# 0827.net
KiCad netlist of a schematic drawn in Altium Designer
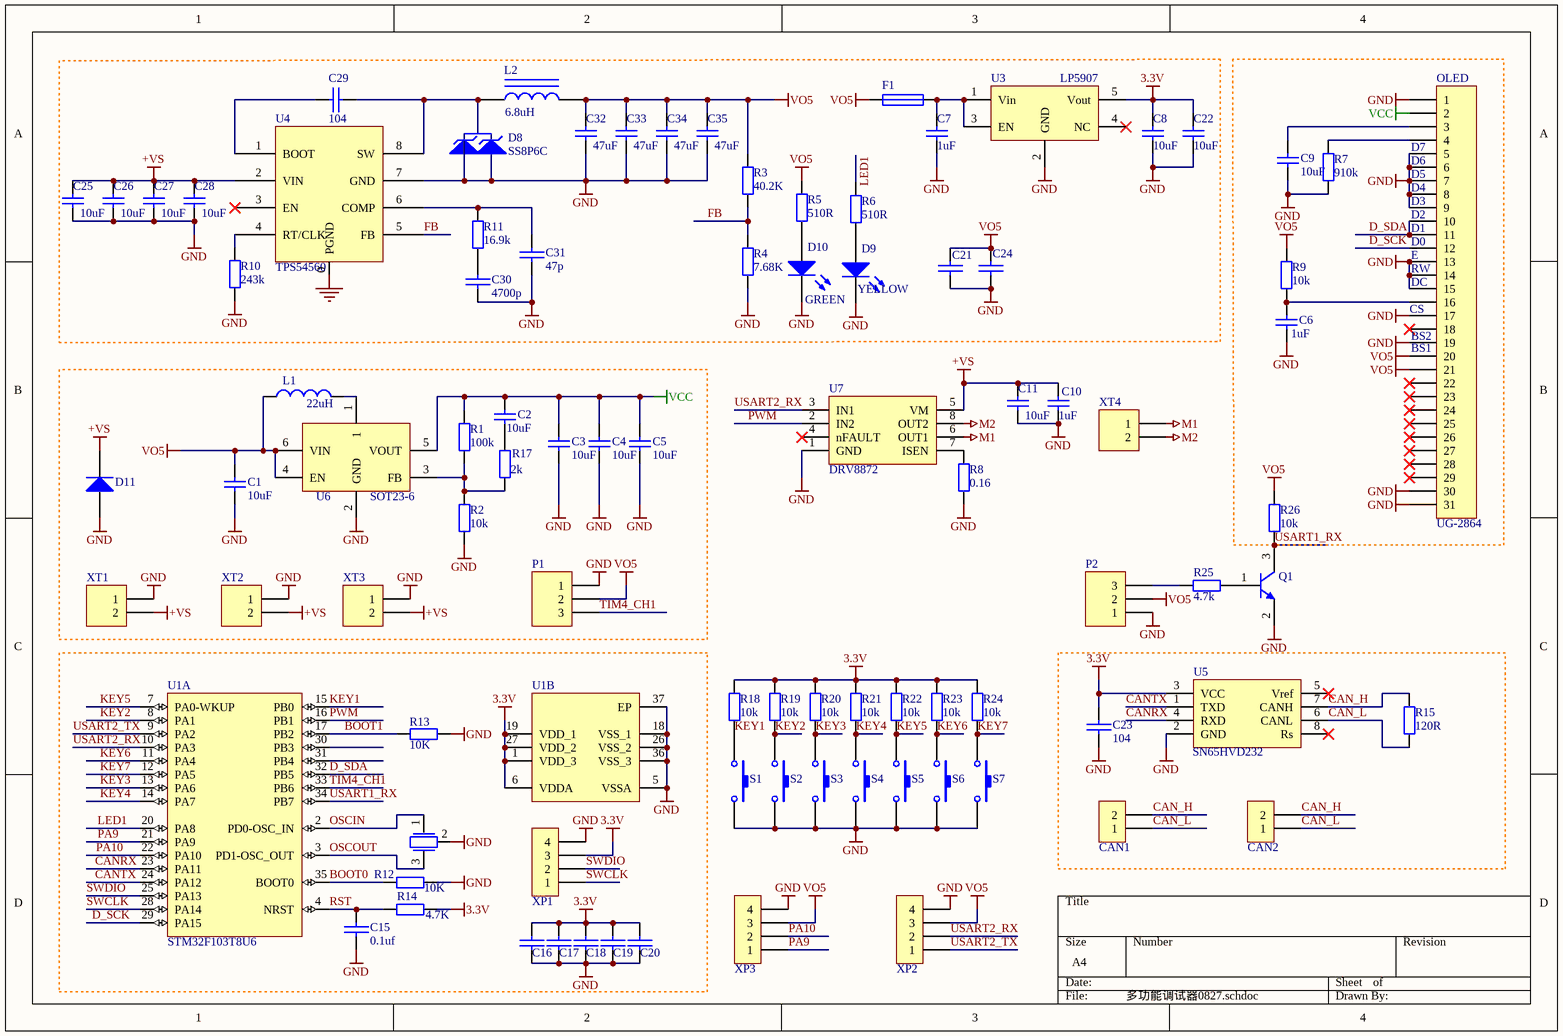
[diagram p0: 多功能调试器0827.schdoc]

(export (version "E")
  (design (tool "Eeschema 10.0.6"))
  (components
    (comp (ref "1")
      (value "~")
      (footprint "XTAL_SMD_3215_2")
      (description "贴片晶振")
      (libsource (lib "Fszhang") (part "XTAL-3PIN"))
    )
    (comp (ref "C1")
      (value "10uF")
      (footprint "1210C")
      (description "Capacitor")
      (fields (field (name "Comment") "2.2uF") (field (name "PUBLISHER") "Altium Limited"))
      (libsource (lib "Miscellaneous Devices") (part "Cap"))
    )
    (comp (ref "C2")
      (value "10uF")
      (footprint "0805C")
      (description "Capacitor")
      (fields (field (name "Comment") "22uF") (field (name "PUBLISHER") "Altium Limited"))
      (libsource (lib "Miscellaneous Devices") (part "Cap"))
    )
    (comp (ref "C3")
      (value "10uF")
      (footprint "0805C")
      (description "Capacitor")
      (fields (field (name "Comment") "22uF") (field (name "PUBLISHER") "Altium Limited"))
      (libsource (lib "Miscellaneous Devices") (part "Cap"))
    )
    (comp (ref "C4")
      (value "10uF")
      (footprint "1210C")
      (description "Capacitor")
      (fields (field (name "Comment") "22uF") (field (name "PUBLISHER") "Altium Limited"))
      (libsource (lib "Miscellaneous Devices") (part "Cap"))
    )
    (comp (ref "C5")
      (value "10uF")
      (footprint "1210C")
      (description "Capacitor")
      (fields (field (name "Comment") "22uF") (field (name "PUBLISHER") "Altium Limited"))
      (libsource (lib "Miscellaneous Devices") (part "Cap"))
    )
    (comp (ref "C6")
      (value "1uF")
      (footprint "0805C")
      (description "Capacitor")
      (fields (field (name "PUBLISHER") "Altium Limited"))
      (libsource (lib "Miscellaneous Devices") (part "Cap"))
    )
    (comp (ref "C7")
      (value "1uF")
      (footprint "0805C")
      (description "Capacitor")
      (fields (field (name "PUBLISHER") "Altium Limited"))
      (libsource (lib "Miscellaneous Devices") (part "Cap"))
    )
    (comp (ref "C8")
      (value "10uF")
      (footprint "0805C")
      (description "Capacitor")
      (fields (field (name "Comment") "1uF") (field (name "PUBLISHER") "Altium Limited"))
      (libsource (lib "Miscellaneous Devices") (part "Cap"))
    )
    (comp (ref "C9")
      (value "10uF")
      (footprint "1210C")
      (description "Capacitor")
      (fields (field (name "Comment") "22uF") (field (name "PUBLISHER") "Altium Limited"))
      (libsource (lib "Miscellaneous Devices") (part "Cap"))
    )
    (comp (ref "C10")
      (value "1uF")
      (footprint "0805C")
      (description "Capacitor")
      (fields (field (name "PUBLISHER") "Altium Limited"))
      (libsource (lib "Miscellaneous Devices") (part "Cap"))
    )
    (comp (ref "C11")
      (value "10uF")
      (footprint "1210C")
      (description "Capacitor")
      (fields (field (name "Comment") "22uF") (field (name "PUBLISHER") "Altium Limited"))
      (libsource (lib "Miscellaneous Devices") (part "Cap"))
    )
    (comp (ref "C15")
      (value "CAP")
      (footprint "0603C")
      (fields (field (name "ALTIUM_UNNAMED_1") "0.1uf"))
      (libsource (lib "My_SCH_Lib") (part "CAP"))
    )
    (comp (ref "C16") (value "~") (footprint "0603C") (libsource (lib "My_SCH_Lib") (part "CAP")))
    (comp (ref "C17") (value "104") (footprint "0603C") (libsource (lib "My_SCH_Lib") (part "CAP")))
    (comp (ref "C18") (value "104") (footprint "0603C") (libsource (lib "My_SCH_Lib") (part "CAP")))
    (comp (ref "C19") (value "104") (footprint "0603C") (libsource (lib "My_SCH_Lib") (part "CAP")))
    (comp (ref "C20") (value "104") (footprint "0603C") (libsource (lib "My_SCH_Lib") (part "CAP")))
    (comp (ref "C21") (value "104") (footprint "0603C") (libsource (lib "My_SCH_Lib") (part "CAP")))
    (comp (ref "C22")
      (value "10uF")
      (footprint "0805C")
      (description "Capacitor")
      (fields (field (name "Comment") "1uF") (field (name "PUBLISHER") "Altium Limited"))
      (libsource (lib "Miscellaneous Devices") (part "Cap"))
    )
    (comp (ref "C23")
      (value "CAP")
      (footprint "0402C")
      (fields (field (name "ALTIUM_UNNAMED_1") "104"))
      (libsource (lib "My_SCH_Lib") (part "CAP"))
    )
    (comp (ref "C24") (value "104") (footprint "0805C") (libsource (lib "My_SCH_Lib") (part "CAP")))
    (comp (ref "C25")
      (value "10uF")
      (footprint "1210C")
      (description "Capacitor")
      (fields (field (name "Comment") "22uF") (field (name "PUBLISHER") "Altium Limited"))
      (libsource (lib "Miscellaneous Devices") (part "Cap"))
    )
    (comp (ref "C26")
      (value "10uF")
      (footprint "1210C")
      (description "Capacitor")
      (fields (field (name "Comment") "22uF") (field (name "PUBLISHER") "Altium Limited"))
      (libsource (lib "Miscellaneous Devices") (part "Cap"))
    )
    (comp (ref "C27")
      (value "10uF")
      (footprint "1210C")
      (description "Capacitor")
      (fields (field (name "Comment") "22uF") (field (name "PUBLISHER") "Altium Limited"))
      (libsource (lib "Miscellaneous Devices") (part "Cap"))
    )
    (comp (ref "C28")
      (value "10uF")
      (footprint "1210C")
      (description "Capacitor")
      (fields (field (name "Comment") "22uF") (field (name "PUBLISHER") "Altium Limited"))
      (libsource (lib "Miscellaneous Devices") (part "Cap"))
    )
    (comp (ref "C29")
      (value "104")
      (footprint "0603C")
      (description "Capacitor")
      (libsource (lib "*") (part "CAP"))
    )
    (comp (ref "C30")
      (value "4700p")
      (footprint "0603C")
      (description "Capacitor")
      (libsource (lib "*") (part "CAP"))
    )
    (comp (ref "C31")
      (value "47p")
      (footprint "0603C")
      (description "Capacitor")
      (libsource (lib "*") (part "CAP"))
    )
    (comp (ref "C32")
      (value "47uF")
      (footprint "1210C")
      (description "Capacitor")
      (fields (field (name "Comment") "22uF") (field (name "PUBLISHER") "Altium Limited"))
      (libsource (lib "Miscellaneous Devices") (part "Cap"))
    )
    (comp (ref "C33")
      (value "47uF")
      (footprint "1210C")
      (description "Capacitor")
      (fields (field (name "Comment") "22uF") (field (name "PUBLISHER") "Altium Limited"))
      (libsource (lib "Miscellaneous Devices") (part "Cap"))
    )
    (comp (ref "C34")
      (value "47uF")
      (footprint "1210C")
      (description "Capacitor")
      (fields (field (name "Comment") "22uF") (field (name "PUBLISHER") "Altium Limited"))
      (libsource (lib "Miscellaneous Devices") (part "Cap"))
    )
    (comp (ref "C35")
      (value "47uF")
      (footprint "1210C")
      (description "Capacitor")
      (fields (field (name "Comment") "22uF") (field (name "PUBLISHER") "Altium Limited"))
      (libsource (lib "Miscellaneous Devices") (part "Cap"))
    )
    (comp (ref "CAN1")
      (value "CAN")
      (footprint "GH1.25-WS-2P")
      (description "jointbar")
      (libsource (lib "Integrated_Library1") (part "SIP2"))
    )
    (comp (ref "CAN2")
      (value "CAN")
      (footprint "GH1.25-WS-2P")
      (description "jointbar")
      (libsource (lib "Integrated_Library1") (part "SIP2"))
    )
    (comp (ref "D8") (value "SS8P6C") (footprint "TO-227") (libsource (lib "步兵2020") (part "SS8P6C")))
    (comp (ref "D9")
      (value "LED0")
      (footprint "LED_0805_B")
      (description "Typical INFRARED GaAs LED")
      (fields (field (name "PUBLISHER") "Altium Limited"))
      (libsource (lib "Miscellaneous Devices") (part "LED0"))
    )
    (comp (ref "D10")
      (value "LED0")
      (footprint "LED_0805_B")
      (description "Typical INFRARED GaAs LED")
      (fields (field (name "PUBLISHER") "Altium Limited"))
      (libsource (lib "Miscellaneous Devices") (part "LED0"))
    )
    (comp (ref "D11")
      (value "~")
      (footprint "DO214_SMA")
      (description "1 Amp General Purpose Rectifier")
      (fields (field (name "PUBLISHER") "Altium Limited"))
      (libsource (lib "Miscellaneous Devices") (part "Diode 1N4001"))
    )
    (comp (ref "F1")
      (value "~")
      (footprint "0805R")
      (description "Fuse")
      (fields (field (name "PUBLISHER") "Altium Limited"))
      (libsource (lib "Miscellaneous Devices") (part "Fuse 1"))
    )
    (comp (ref "L1")
      (value "22uH")
      (footprint "L6×6")
      (description "Inductor")
      (fields (field (name "Comment") "10uH") (field (name "PUBLISHER") "Altium Limited"))
      (libsource (lib "Miscellaneous Devices") (part "Inductor"))
    )
    (comp (ref "L2")
      (value "6.8uH")
      (footprint "L7-7")
      (description "Magnetic-Core Inductor")
      (fields (field (name "PUBLISHER") "Altium Limited"))
      (libsource (lib "Miscellaneous Devices") (part "Inductor Iron"))
    )
    (comp (ref "OLED")
      (value "UG-2864")
      (footprint "OLED")
      (description "Header, 30-Pin")
      (fields (field (name "PUBLISHER") "Altium Limited"))
      (libsource (lib "VFD25650") (part "Header 30"))
    )
    (comp (ref "P1")
      (value "~")
      (footprint "HDR2.54-LI-3P")
      (description "Header, 3-Pin")
      (fields (field (name "PUBLISHER") "Altium Limited"))
      (libsource (lib "") (part "Header 3_1"))
    )
    (comp (ref "P2")
      (value "~")
      (footprint "HDR2.54-LI-3P")
      (description "Header, 3-Pin")
      (fields (field (name "PUBLISHER") "Altium Limited"))
      (libsource (lib "Miscellaneous Connectors") (part "Header 3"))
    )
    (comp (ref "Q1")
      (value "~")
      (footprint "SOT23_3")
      (description "NPN Bipolar Transistor")
      (fields (field (name "PUBLISHER") "Altium Limited"))
      (libsource (lib "Miscellaneous Devices") (part "NPN"))
    )
    (comp (ref "R1")
      (value "100k")
      (footprint "0805R")
      (description "Resistor")
      (fields (field (name "PUBLISHER") "Altium Limited"))
      (libsource (lib "") (part "Res2_2"))
    )
    (comp (ref "R2")
      (value "10k")
      (footprint "0805R")
      (description "Resistor")
      (fields (field (name "PUBLISHER") "Altium Limited"))
      (libsource (lib "") (part "Res2_2"))
    )
    (comp (ref "R3")
      (value "40.2K")
      (footprint "0603R")
      (description "贴片电阻")
      (fields (field (name "Comment") "Res1") (field (name "PUBLISHER") "Altium Limited"))
      (libsource (lib "Fszhang") (part "Res1"))
    )
    (comp (ref "R4")
      (value "7.68K")
      (footprint "0603R")
      (description "贴片电阻")
      (fields (field (name "Comment") "Res1") (field (name "PUBLISHER") "Altium Limited"))
      (libsource (lib "Fszhang") (part "Res1"))
    )
    (comp (ref "R5")
      (value "510R")
      (footprint "0805R")
      (description "贴片电阻")
      (fields (field (name "Comment") "Res1") (field (name "PUBLISHER") "Altium Limited"))
      (libsource (lib "Fszhang") (part "Res1"))
    )
    (comp (ref "R6")
      (value "510R")
      (footprint "0805R")
      (description "贴片电阻")
      (fields (field (name "Comment") "Res1") (field (name "PUBLISHER") "Altium Limited"))
      (libsource (lib "Fszhang") (part "Res1"))
    )
    (comp (ref "R7")
      (value "910k")
      (footprint "0805R")
      (description "Resistor")
      (fields (field (name "PUBLISHER") "Altium Limited"))
      (libsource (lib "") (part "Res2_2"))
    )
    (comp (ref "R8")
      (value "0.16")
      (footprint "1210R")
      (description "Resistor")
      (fields (field (name "PUBLISHER") "Altium Limited"))
      (libsource (lib "") (part "Res2_2"))
    )
    (comp (ref "R9")
      (value "10k")
      (footprint "0805R")
      (description "Resistor")
      (fields (field (name "PUBLISHER") "Altium Limited"))
      (libsource (lib "2017.2步兵主控") (part "Res2"))
    )
    (comp (ref "R10")
      (value "243k")
      (footprint "0603R")
      (description "Resistor")
      (fields (field (name "PUBLISHER") "Altium Limited"))
      (libsource (lib "2017.2步兵主控") (part "Res2"))
    )
    (comp (ref "R11")
      (value "16.9k")
      (footprint "0603R")
      (description "Resistor")
      (fields (field (name "PUBLISHER") "Altium Limited"))
      (libsource (lib "2017.2步兵主控") (part "Res2"))
    )
    (comp (ref "R12")
      (value "10K")
      (footprint "0603R")
      (description "贴片电阻")
      (fields (field (name "Comment") "Res1") (field (name "PUBLISHER") "Altium Limited"))
      (libsource (lib "") (part "Res1_1"))
    )
    (comp (ref "R13")
      (value "10K")
      (footprint "0603R")
      (description "贴片电阻")
      (fields (field (name "Comment") "Res1") (field (name "PUBLISHER") "Altium Limited"))
      (libsource (lib "") (part "Res1_1"))
    )
    (comp (ref "R14")
      (value "4.7K")
      (footprint "0603R")
      (description "贴片电阻")
      (fields (field (name "Comment") "Res1") (field (name "PUBLISHER") "Altium Limited"))
      (libsource (lib "") (part "Res1_1"))
    )
    (comp (ref "R15")
      (value "120R")
      (footprint "0603C")
      (description "贴片电阻")
      (fields (field (name "Comment") "Res1") (field (name "PUBLISHER") "Altium Limited"))
      (libsource (lib "Fszhang") (part "Res1"))
    )
    (comp (ref "R17")
      (value "2k")
      (footprint "0805R")
      (description "Resistor")
      (fields (field (name "PUBLISHER") "Altium Limited"))
      (libsource (lib "") (part "Res2_2"))
    )
    (comp (ref "R18")
      (value "10k")
      (footprint "0805R")
      (description "Resistor")
      (fields (field (name "PUBLISHER") "Altium Limited"))
      (libsource (lib "2017.2步兵主控") (part "Res2"))
    )
    (comp (ref "R19")
      (value "10k")
      (footprint "0805R")
      (description "Resistor")
      (fields (field (name "PUBLISHER") "Altium Limited"))
      (libsource (lib "2017.2步兵主控") (part "Res2"))
    )
    (comp (ref "R20")
      (value "10k")
      (footprint "0805R")
      (description "Resistor")
      (fields (field (name "PUBLISHER") "Altium Limited"))
      (libsource (lib "2017.2步兵主控") (part "Res2"))
    )
    (comp (ref "R21")
      (value "10k")
      (footprint "0805R")
      (description "Resistor")
      (fields (field (name "PUBLISHER") "Altium Limited"))
      (libsource (lib "2017.2步兵主控") (part "Res2"))
    )
    (comp (ref "R22")
      (value "10k")
      (footprint "0805R")
      (description "Resistor")
      (fields (field (name "PUBLISHER") "Altium Limited"))
      (libsource (lib "2017.2步兵主控") (part "Res2"))
    )
    (comp (ref "R23")
      (value "10k")
      (footprint "0805R")
      (description "Resistor")
      (fields (field (name "PUBLISHER") "Altium Limited"))
      (libsource (lib "2017.2步兵主控") (part "Res2"))
    )
    (comp (ref "R24")
      (value "10k")
      (footprint "0805R")
      (description "Resistor")
      (fields (field (name "PUBLISHER") "Altium Limited"))
      (libsource (lib "2017.2步兵主控") (part "Res2"))
    )
    (comp (ref "R25")
      (value "4.7k")
      (footprint "0805R")
      (description "Resistor")
      (fields (field (name "PUBLISHER") "Altium Limited"))
      (libsource (lib "") (part "Res2_1"))
    )
    (comp (ref "R26")
      (value "10k")
      (footprint "0805R")
      (description "Resistor")
      (fields (field (name "PUBLISHER") "Altium Limited"))
      (libsource (lib "") (part "Res2_2"))
    )
    (comp (ref "S1")
      (value "SW-PB")
      (footprint "SW_PB_6*6")
      (description "Switch")
      (fields (field (name "PUBLISHER") "Altium Limited"))
      (libsource (lib "") (part "SW-PB_1"))
    )
    (comp (ref "S2")
      (value "SW-PB")
      (footprint "SW_PB_6*6")
      (description "Switch")
      (fields (field (name "PUBLISHER") "Altium Limited"))
      (libsource (lib "") (part "SW-PB_1"))
    )
    (comp (ref "S3")
      (value "SW-PB")
      (footprint "BUT12/B3F")
      (description "Switch")
      (fields (field (name "PUBLISHER") "Altium Limited"))
      (libsource (lib "Miscellaneous Devices") (part "SW-PB"))
    )
    (comp (ref "S4")
      (value "SW-PB")
      (footprint "BUT12/B3F")
      (description "Switch")
      (fields (field (name "PUBLISHER") "Altium Limited"))
      (libsource (lib "Miscellaneous Devices") (part "SW-PB"))
    )
    (comp (ref "S5")
      (value "SW-PB")
      (footprint "BUT12/B3F")
      (description "Switch")
      (fields (field (name "PUBLISHER") "Altium Limited"))
      (libsource (lib "Miscellaneous Devices") (part "SW-PB"))
    )
    (comp (ref "S6")
      (value "SW-PB")
      (footprint "BUT12/B3F")
      (description "Switch")
      (fields (field (name "PUBLISHER") "Altium Limited"))
      (libsource (lib "Miscellaneous Devices") (part "SW-PB"))
    )
    (comp (ref "S7")
      (value "SW-PB")
      (footprint "BUT12/B3F")
      (description "Switch")
      (fields (field (name "PUBLISHER") "Altium Limited"))
      (libsource (lib "Miscellaneous Devices") (part "SW-PB"))
    )
    (comp (ref "U1")
      (value "STM32F103T8U6")
      (footprint "VFQN36_N")
      (fields (field (name "PARTNUMBER") "STM32F103TBU6"))
      (libsource (lib "多功能调试器V1.0") (part "STM32F103TBU6"))
    )
    (comp (ref "U3") (value "LP5907") (footprint "SOT23_5") (libsource (lib "VFD25650") (part "LP5907")))
    (comp (ref "U4") (value "TPS54560") (footprint "SOIC8E") (libsource (lib "yuanlitu") (part "TPS54560")))
    (comp (ref "U5")
      (value "SN65HVD232")
      (footprint "SOp8")
      (libsource (lib "Robomasters") (part "SN65HVD232"))
    )
    (comp (ref "U6")
      (value "SOT23-6")
      (footprint "SOT23_6")
      (libsource (lib "yuanlitu") (part "未知电源芯片SOT23-6"))
    )
    (comp (ref "U7")
      (value "DRV8872")
      (footprint "SOIC8E")
      (libsource (lib "多功能调试器V1.0") (part "SN65HVD232_1"))
    )
    (comp (ref "XP1")
      (value "CON4")
      (footprint "GH1.25-WS-4P")
      (description "Connector")
      (libsource (lib "POWER_S_M") (part "CON4"))
    )
    (comp (ref "XP2")
      (value "CON4")
      (footprint "GH1.25-WS-4P")
      (description "Connector")
      (libsource (lib "POWER_S_M") (part "CON4"))
    )
    (comp (ref "XP3")
      (value "CON4")
      (footprint "GH1.25-WS-4P")
      (description "Connector")
      (libsource (lib "POWER_S_M") (part "CON4"))
    )
    (comp (ref "XT1")
      (value "~")
      (footprint "XT30PW-M")
      (description "Header, 2-Pin")
      (fields (field (name "PUBLISHER") "Altium Limited"))
      (libsource (lib "2017.2步兵主控") (part "Header 2"))
    )
    (comp (ref "XT2")
      (value "~")
      (footprint "XT30PW-M")
      (description "Header, 2-Pin")
      (fields (field (name "PUBLISHER") "Altium Limited"))
      (libsource (lib "2017.2步兵主控") (part "Header 2"))
    )
    (comp (ref "XT3")
      (value "~")
      (footprint "XT30PW-M")
      (description "Header, 2-Pin")
      (fields (field (name "PUBLISHER") "Altium Limited"))
      (libsource (lib "2017.2步兵主控") (part "Header 2"))
    )
    (comp (ref "XT4")
      (value "~")
      (footprint "XT30PW-M")
      (description "Header, 2-Pin")
      (fields (field (name "PUBLISHER") "Altium Limited"))
      (libsource (lib "2017.2步兵主控") (part "Header 2"))
    )
  )
  (nets
    (net (code "1") (name "+VS") (class "Default")
      (node (ref "C10") (pin "2") (pinfunction "2_2") (pintype "passive"))
      (node (ref "C11") (pin "1") (pinfunction "1_1") (pintype "passive"))
      (node (ref "C25") (pin "1") (pinfunction "1_1") (pintype "passive"))
      (node (ref "C26") (pin "1") (pinfunction "1_1") (pintype "passive"))
      (node (ref "C27") (pin "1") (pinfunction "1_1") (pintype "passive"))
      (node (ref "C28") (pin "1") (pinfunction "1_1") (pintype "passive"))
      (node (ref "D11") (pin "2") (pinfunction "K_2") (pintype "passive"))
      (node (ref "U4") (pin "2") (pinfunction "VIN_2") (pintype "passive"))
      (node (ref "U7") (pin "5") (pinfunction "VM_5") (pintype "passive"))
      (node (ref "XT1") (pin "2") (pinfunction "2_2") (pintype "passive"))
      (node (ref "XT2") (pin "2") (pinfunction "2_2") (pintype "passive"))
      (node (ref "XT3") (pin "2") (pinfunction "2_2") (pintype "passive"))
    )
    (net (code "2") (name "/BOOT0") (class "Default")
      (node (ref "R12") (pin "2") (pinfunction "2_2") (pintype "passive"))
      (node (ref "U1") (pin "35") (pinfunction "BOOT0_35") (pintype "bidirectional"))
    )
    (net (code "3") (name "/BOOT1") (class "Default")
      (node (ref "R13") (pin "2") (pinfunction "2_2") (pintype "passive"))
      (node (ref "U1") (pin "17") (pinfunction "PB2_17") (pintype "bidirectional"))
    )
    (net (code "4") (name "/CANRX") (class "Default")
      (node (ref "U1") (pin "23") (pinfunction "PA11_23") (pintype "bidirectional"))
      (node (ref "U5") (pin "4") (pinfunction "RXD_4") (pintype "passive"))
    )
    (net (code "5") (name "/CANTX") (class "Default")
      (node (ref "U1") (pin "24") (pinfunction "PA12_24") (pintype "bidirectional"))
      (node (ref "U5") (pin "1") (pinfunction "TXD_1") (pintype "passive"))
    )
    (net (code "6") (name "/CAN_H") (class "Default")
      (node (ref "CAN1") (pin "2") (pinfunction "2_2") (pintype "passive"))
      (node (ref "CAN2") (pin "2") (pinfunction "2_2") (pintype "passive"))
      (node (ref "R15") (pin "1") (pinfunction "1_1") (pintype "passive"))
      (node (ref "U5") (pin "7") (pinfunction "CANH_7") (pintype "passive"))
    )
    (net (code "7") (name "/CAN_L") (class "Default")
      (node (ref "CAN1") (pin "1") (pinfunction "1_1") (pintype "passive"))
      (node (ref "CAN2") (pin "1") (pinfunction "1_1") (pintype "passive"))
      (node (ref "R15") (pin "2") (pinfunction "2_2") (pintype "passive"))
      (node (ref "U5") (pin "6") (pinfunction "CANL_6") (pintype "passive"))
    )
    (net (code "8") (name "/D_SCK") (class "Default")
      (node (ref "OLED") (pin "12") (pinfunction "12_12") (pintype "passive"))
      (node (ref "U1") (pin "29") (pinfunction "PA15_29") (pintype "bidirectional"))
    )
    (net (code "9") (name "/D_SDA") (class "Default")
      (node (ref "OLED") (pin "10") (pinfunction "10_10") (pintype "passive"))
      (node (ref "OLED") (pin "11") (pinfunction "11_11") (pintype "passive"))
      (node (ref "U1") (pin "32") (pinfunction "PB5_32") (pintype "bidirectional"))
    )
    (net (code "10") (name "/FB") (class "Default")
      (node (ref "R3") (pin "2") (pinfunction "2_2") (pintype "passive"))
      (node (ref "R4") (pin "1") (pinfunction "1_1") (pintype "passive"))
      (node (ref "U4") (pin "5") (pinfunction "FB_5") (pintype "passive"))
    )
    (net (code "11") (name "/KEY1") (class "Default")
      (node (ref "R18") (pin "2") (pinfunction "2_2") (pintype "passive"))
      (node (ref "S1") (pin "1") (pinfunction "1_1") (pintype "passive"))
      (node (ref "U1") (pin "15") (pinfunction "PB0_15") (pintype "bidirectional"))
    )
    (net (code "12") (name "/KEY2") (class "Default")
      (node (ref "R19") (pin "2") (pinfunction "2_2") (pintype "passive"))
      (node (ref "S2") (pin "1") (pinfunction "1_1") (pintype "passive"))
      (node (ref "U1") (pin "8") (pinfunction "PA1_8") (pintype "bidirectional"))
    )
    (net (code "13") (name "/KEY3") (class "Default")
      (node (ref "R20") (pin "2") (pinfunction "2_2") (pintype "passive"))
      (node (ref "S3") (pin "1") (pinfunction "1_1") (pintype "passive"))
      (node (ref "U1") (pin "13") (pinfunction "PA6_13") (pintype "bidirectional"))
    )
    (net (code "14") (name "/KEY4") (class "Default")
      (node (ref "R21") (pin "2") (pinfunction "2_2") (pintype "passive"))
      (node (ref "S4") (pin "1") (pinfunction "1_1") (pintype "passive"))
      (node (ref "U1") (pin "14") (pinfunction "PA7_14") (pintype "bidirectional"))
    )
    (net (code "15") (name "/KEY5") (class "Default")
      (node (ref "R22") (pin "2") (pinfunction "2_2") (pintype "passive"))
      (node (ref "S5") (pin "1") (pinfunction "1_1") (pintype "passive"))
      (node (ref "U1") (pin "7") (pinfunction "PA0-WKUP_7") (pintype "bidirectional"))
    )
    (net (code "16") (name "/KEY6") (class "Default")
      (node (ref "R23") (pin "2") (pinfunction "2_2") (pintype "passive"))
      (node (ref "S6") (pin "1") (pinfunction "1_1") (pintype "passive"))
      (node (ref "U1") (pin "11") (pinfunction "PA4_11") (pintype "bidirectional"))
    )
    (net (code "17") (name "/KEY7") (class "Default")
      (node (ref "R24") (pin "2") (pinfunction "2_2") (pintype "passive"))
      (node (ref "S7") (pin "1") (pinfunction "1_1") (pintype "passive"))
      (node (ref "U1") (pin "12") (pinfunction "PA5_12") (pintype "bidirectional"))
    )
    (net (code "18") (name "/LED1") (class "Default")
      (node (ref "R6") (pin "1") (pinfunction "1_1") (pintype "passive"))
      (node (ref "U1") (pin "20") (pinfunction "PA8_20") (pintype "bidirectional"))
    )
    (net (code "19") (name "/OSCIN") (class "Default")
      (node (ref "1") (pin "1") (pinfunction "1_1") (pintype "passive"))
      (node (ref "U1") (pin "2") (pinfunction "PD0-OSC_IN_2") (pintype "bidirectional"))
    )
    (net (code "20") (name "/OSCOUT") (class "Default")
      (node (ref "1") (pin "3") (pinfunction "3_3") (pintype "passive"))
      (node (ref "U1") (pin "3") (pinfunction "PD1-OSC_OUT_3") (pintype "bidirectional"))
    )
    (net (code "21") (name "/PA9") (class "Default")
      (node (ref "U1") (pin "21") (pinfunction "PA9_21") (pintype "bidirectional"))
      (node (ref "XP3") (pin "1") (pinfunction "1_1") (pintype "passive"))
    )
    (net (code "22") (name "/PA10") (class "Default")
      (node (ref "U1") (pin "22") (pinfunction "PA10_22") (pintype "bidirectional"))
      (node (ref "XP3") (pin "2") (pinfunction "2_2") (pintype "passive"))
    )
    (net (code "23") (name "/PWM") (class "Default")
      (node (ref "U1") (pin "16") (pinfunction "PB1_16") (pintype "bidirectional"))
      (node (ref "U7") (pin "2") (pinfunction "IN2_2") (pintype "passive"))
    )
    (net (code "24") (name "/RST") (class "Default")
      (node (ref "C15") (pin "1") (pinfunction "1_1") (pintype "passive"))
      (node (ref "R14") (pin "2") (pinfunction "2_2") (pintype "passive"))
      (node (ref "U1") (pin "4") (pinfunction "NRST_4") (pintype "bidirectional"))
    )
    (net (code "25") (name "/SWCLK") (class "Default")
      (node (ref "U1") (pin "28") (pinfunction "PA14_28") (pintype "bidirectional"))
      (node (ref "XP1") (pin "1") (pinfunction "1_1") (pintype "passive"))
    )
    (net (code "26") (name "/SWDIO") (class "Default")
      (node (ref "U1") (pin "25") (pinfunction "PA13_25") (pintype "bidirectional"))
      (node (ref "XP1") (pin "2") (pinfunction "2_2") (pintype "passive"))
    )
    (net (code "27") (name "/TIM4_CH1") (class "Default")
      (node (ref "P1") (pin "3") (pinfunction "3_3") (pintype "passive"))
      (node (ref "U1") (pin "33") (pinfunction "PB6_33") (pintype "bidirectional"))
    )
    (net (code "28") (name "/USART1_RX") (class "Default")
      (node (ref "Q1") (pin "3") (pinfunction "C_3") (pintype "passive"))
      (node (ref "R26") (pin "1") (pinfunction "1_1") (pintype "passive"))
      (node (ref "U1") (pin "34") (pinfunction "PB7_34") (pintype "bidirectional"))
    )
    (net (code "29") (name "/USART2_RX") (class "Default")
      (node (ref "U1") (pin "10") (pinfunction "PA3_10") (pintype "bidirectional"))
      (node (ref "U7") (pin "3") (pinfunction "IN1_3") (pintype "passive"))
      (node (ref "XP2") (pin "2") (pinfunction "2_2") (pintype "passive"))
    )
    (net (code "30") (name "/USART2_TX") (class "Default")
      (node (ref "U1") (pin "9") (pinfunction "PA2_9") (pintype "bidirectional"))
      (node (ref "XP2") (pin "1") (pinfunction "1_1") (pintype "passive"))
    )
    (net (code "31") (name "3.3V") (class "Default")
      (node (ref "C16") (pin "1") (pinfunction "1_1") (pintype "passive"))
      (node (ref "C17") (pin "1") (pinfunction "1_1") (pintype "passive"))
      (node (ref "C18") (pin "1") (pinfunction "1_1") (pintype "passive"))
      (node (ref "C19") (pin "1") (pinfunction "1_1") (pintype "passive"))
      (node (ref "C20") (pin "1") (pinfunction "1_1") (pintype "passive"))
      (node (ref "C22") (pin "2") (pinfunction "2_2") (pintype "passive"))
      (node (ref "C23") (pin "1") (pinfunction "1_1") (pintype "passive"))
      (node (ref "C8") (pin "2") (pinfunction "2_2") (pintype "passive"))
      (node (ref "R14") (pin "1") (pinfunction "1_1") (pintype "passive"))
      (node (ref "R18") (pin "1") (pinfunction "1_1") (pintype "passive"))
      (node (ref "R19") (pin "1") (pinfunction "1_1") (pintype "passive"))
      (node (ref "R20") (pin "1") (pinfunction "1_1") (pintype "passive"))
      (node (ref "R21") (pin "1") (pinfunction "1_1") (pintype "passive"))
      (node (ref "R22") (pin "1") (pinfunction "1_1") (pintype "passive"))
      (node (ref "R23") (pin "1") (pinfunction "1_1") (pintype "passive"))
      (node (ref "R24") (pin "1") (pinfunction "1_1") (pintype "passive"))
      (node (ref "U1") (pin "1") (pinfunction "VDD_3_1") (pintype "power_in"))
      (node (ref "U1") (pin "19") (pinfunction "VDD_1_19") (pintype "power_in"))
      (node (ref "U1") (pin "27") (pinfunction "VDD_2_27") (pintype "power_in"))
      (node (ref "U1") (pin "6") (pinfunction "VDDA_6") (pintype "power_in"))
      (node (ref "U3") (pin "5") (pinfunction "Vout_5") (pintype "passive"))
      (node (ref "U5") (pin "3") (pinfunction "VCC_3") (pintype "passive"))
      (node (ref "XP1") (pin "3") (pinfunction "3_3") (pintype "passive"))
    )
    (net (code "32") (name "GND") (class "Default")
      (node (ref "1") (pin "2") (pinfunction "2_2") (pintype "passive"))
      (node (ref "C1") (pin "1") (pinfunction "1_1") (pintype "passive"))
      (node (ref "C10") (pin "1") (pinfunction "1_1") (pintype "passive"))
      (node (ref "C11") (pin "2") (pinfunction "2_2") (pintype "passive"))
      (node (ref "C15") (pin "2") (pinfunction "2_2") (pintype "passive"))
      (node (ref "C16") (pin "2") (pinfunction "2_2") (pintype "passive"))
      (node (ref "C17") (pin "2") (pinfunction "2_2") (pintype "passive"))
      (node (ref "C18") (pin "2") (pinfunction "2_2") (pintype "passive"))
      (node (ref "C19") (pin "2") (pinfunction "2_2") (pintype "passive"))
      (node (ref "C20") (pin "2") (pinfunction "2_2") (pintype "passive"))
      (node (ref "C21") (pin "2") (pinfunction "2_2") (pintype "passive"))
      (node (ref "C22") (pin "1") (pinfunction "1_1") (pintype "passive"))
      (node (ref "C23") (pin "2") (pinfunction "2_2") (pintype "passive"))
      (node (ref "C24") (pin "2") (pinfunction "2_2") (pintype "passive"))
      (node (ref "C25") (pin "2") (pinfunction "2_2") (pintype "passive"))
      (node (ref "C26") (pin "2") (pinfunction "2_2") (pintype "passive"))
      (node (ref "C27") (pin "2") (pinfunction "2_2") (pintype "passive"))
      (node (ref "C28") (pin "2") (pinfunction "2_2") (pintype "passive"))
      (node (ref "C3") (pin "1") (pinfunction "1_1") (pintype "passive"))
      (node (ref "C30") (pin "1") (pinfunction "1_1") (pintype "passive"))
      (node (ref "C31") (pin "1") (pinfunction "1_1") (pintype "passive"))
      (node (ref "C32") (pin "2") (pinfunction "2_2") (pintype "passive"))
      (node (ref "C33") (pin "2") (pinfunction "2_2") (pintype "passive"))
      (node (ref "C34") (pin "2") (pinfunction "2_2") (pintype "passive"))
      (node (ref "C35") (pin "2") (pinfunction "2_2") (pintype "passive"))
      (node (ref "C4") (pin "1") (pinfunction "1_1") (pintype "passive"))
      (node (ref "C5") (pin "1") (pinfunction "1_1") (pintype "passive"))
      (node (ref "C6") (pin "1") (pinfunction "1_1") (pintype "passive"))
      (node (ref "C7") (pin "1") (pinfunction "1_1") (pintype "passive"))
      (node (ref "C8") (pin "1") (pinfunction "1_1") (pintype "passive"))
      (node (ref "C9") (pin "1") (pinfunction "1_1") (pintype "passive"))
      (node (ref "D10") (pin "2") (pinfunction "K_2") (pintype "passive"))
      (node (ref "D11") (pin "1") (pinfunction "A_1") (pintype "passive"))
      (node (ref "D8") (pin "1") (pinfunction "A_1") (pintype "passive"))
      (node (ref "D8") (pin "2") (pinfunction "A_2") (pintype "passive"))
      (node (ref "D9") (pin "2") (pinfunction "K_2") (pintype "passive"))
      (node (ref "OLED") (pin "1") (pinfunction "1_1") (pintype "passive"))
      (node (ref "OLED") (pin "13") (pinfunction "13_13") (pintype "passive"))
      (node (ref "OLED") (pin "14") (pinfunction "14_14") (pintype "passive"))
      (node (ref "OLED") (pin "15") (pinfunction "15_15") (pintype "passive"))
      (node (ref "OLED") (pin "17") (pinfunction "17_17") (pintype "passive"))
      (node (ref "OLED") (pin "19") (pinfunction "19_19") (pintype "passive"))
      (node (ref "OLED") (pin "30") (pinfunction "30_30") (pintype "passive"))
      (node (ref "OLED") (pin "31") (pinfunction "31_31") (pintype "passive"))
      (node (ref "OLED") (pin "5") (pinfunction "5_5") (pintype "passive"))
      (node (ref "OLED") (pin "6") (pinfunction "6_6") (pintype "passive"))
      (node (ref "OLED") (pin "7") (pinfunction "7_7") (pintype "passive"))
      (node (ref "OLED") (pin "8") (pinfunction "8_8") (pintype "passive"))
      (node (ref "OLED") (pin "9") (pinfunction "9_9") (pintype "passive"))
      (node (ref "P1") (pin "1") (pinfunction "1_1") (pintype "passive"))
      (node (ref "P2") (pin "1") (pinfunction "1_1") (pintype "passive"))
      (node (ref "Q1") (pin "2") (pinfunction "E_2") (pintype "passive"))
      (node (ref "R10") (pin "2") (pinfunction "2_2") (pintype "passive"))
      (node (ref "R12") (pin "1") (pinfunction "1_1") (pintype "passive"))
      (node (ref "R13") (pin "1") (pinfunction "1_1") (pintype "passive"))
      (node (ref "R2") (pin "1") (pinfunction "1_1") (pintype "passive"))
      (node (ref "R4") (pin "2") (pinfunction "2_2") (pintype "passive"))
      (node (ref "R7") (pin "1") (pinfunction "1_1") (pintype "passive"))
      (node (ref "R8") (pin "1") (pinfunction "1_1") (pintype "passive"))
      (node (ref "S1") (pin "2") (pinfunction "2_2") (pintype "passive"))
      (node (ref "S2") (pin "2") (pinfunction "2_2") (pintype "passive"))
      (node (ref "S3") (pin "3") (pinfunction "2_3") (pintype "passive"))
      (node (ref "S4") (pin "3") (pinfunction "2_3") (pintype "passive"))
      (node (ref "S5") (pin "3") (pinfunction "2_3") (pintype "passive"))
      (node (ref "S6") (pin "3") (pinfunction "2_3") (pintype "passive"))
      (node (ref "S7") (pin "3") (pinfunction "2_3") (pintype "passive"))
      (node (ref "U1") (pin "18") (pinfunction "VSS_1_18") (pintype "power_in"))
      (node (ref "U1") (pin "26") (pinfunction "VSS_2_26") (pintype "power_in"))
      (node (ref "U1") (pin "36") (pinfunction "VSS_3_36") (pintype "power_in"))
      (node (ref "U1") (pin "37") (pinfunction "EP_37") (pintype "power_in"))
      (node (ref "U1") (pin "5") (pinfunction "VSSA_5") (pintype "power_in"))
      (node (ref "U3") (pin "2") (pinfunction "GND_2") (pintype "passive"))
      (node (ref "U4") (pin "0") (pinfunction "PGND_0") (pintype "passive"))
      (node (ref "U4") (pin "7") (pinfunction "GND_7") (pintype "passive"))
      (node (ref "U5") (pin "2") (pinfunction "GND_2") (pintype "passive"))
      (node (ref "U6") (pin "2") (pinfunction "GND_2") (pintype "passive"))
      (node (ref "U7") (pin "1") (pinfunction "GND_1") (pintype "passive"))
      (node (ref "XP1") (pin "4") (pinfunction "4_4") (pintype "passive"))
      (node (ref "XP2") (pin "4") (pinfunction "4_4") (pintype "passive"))
      (node (ref "XP3") (pin "4") (pinfunction "4_4") (pintype "passive"))
      (node (ref "XT1") (pin "1") (pinfunction "1_1") (pintype "passive"))
      (node (ref "XT2") (pin "1") (pinfunction "1_1") (pintype "passive"))
      (node (ref "XT3") (pin "1") (pinfunction "1_1") (pintype "passive"))
    )
    (net (code "33") (name "M1") (class "Default")
      (node (ref "U7") (pin "6") (pinfunction "OUT1_6") (pintype "passive"))
      (node (ref "XT4") (pin "1") (pinfunction "1_1") (pintype "passive"))
    )
    (net (code "34") (name "M2") (class "Default")
      (node (ref "U7") (pin "8") (pinfunction "OUT2_8") (pintype "passive"))
      (node (ref "XT4") (pin "2") (pinfunction "2_2") (pintype "passive"))
    )
    (net (code "35") (name "Net-(C2-Pad1)") (class "Default")
      (node (ref "C2") (pin "1") (pinfunction "1_1") (pintype "passive"))
      (node (ref "R17") (pin "2") (pinfunction "2_2") (pintype "passive"))
    )
    (net (code "36") (name "Net-(C6-Pad2)") (class "Default")
      (node (ref "C6") (pin "2") (pinfunction "2_2") (pintype "passive"))
      (node (ref "OLED") (pin "16") (pinfunction "16_16") (pintype "passive"))
      (node (ref "R9") (pin "2") (pinfunction "2_2") (pintype "passive"))
    )
    (net (code "37") (name "Net-(C9-Pad2)") (class "Default")
      (node (ref "C9") (pin "2") (pinfunction "2_2") (pintype "passive"))
      (node (ref "OLED") (pin "3") (pinfunction "3_3") (pintype "passive"))
    )
    (net (code "38") (name "Net-(C30-Pad2)") (class "Default")
      (node (ref "C30") (pin "2") (pinfunction "2_2") (pintype "passive"))
      (node (ref "R11") (pin "2") (pinfunction "2_2") (pintype "passive"))
    )
    (net (code "39") (name "Net-(D8-K)") (class "Default")
      (node (ref "C29") (pin "2") (pinfunction "2_2") (pintype "passive"))
      (node (ref "D8") (pin "3") (pinfunction "K_3") (pintype "passive"))
      (node (ref "L2") (pin "1") (pinfunction "1_1") (pintype "passive"))
      (node (ref "U4") (pin "8") (pinfunction "SW_8") (pintype "passive"))
    )
    (net (code "40") (name "Net-(D9-A)") (class "Default")
      (node (ref "D9") (pin "1") (pinfunction "A_1") (pintype "passive"))
      (node (ref "R6") (pin "2") (pinfunction "2_2") (pintype "passive"))
    )
    (net (code "41") (name "Net-(D10-A)") (class "Default")
      (node (ref "D10") (pin "1") (pinfunction "A_1") (pintype "passive"))
      (node (ref "R5") (pin "2") (pinfunction "2_2") (pintype "passive"))
    )
    (net (code "42") (name "Net-(L1-Pad2)") (class "Default")
      (node (ref "L1") (pin "2") (pinfunction "2_2") (pintype "passive"))
      (node (ref "U6") (pin "1") (pinfunction "1_1") (pintype "passive"))
    )
    (net (code "43") (name "Net-(OLED-Pad4)") (class "Default")
      (node (ref "OLED") (pin "4") (pinfunction "4_4") (pintype "passive"))
      (node (ref "R7") (pin "2") (pinfunction "2_2") (pintype "passive"))
    )
    (net (code "44") (name "Net-(P2-Pad3)") (class "Default")
      (node (ref "P2") (pin "3") (pinfunction "3_3") (pintype "passive"))
      (node (ref "R25") (pin "1") (pinfunction "1_1") (pintype "passive"))
    )
    (net (code "45") (name "Net-(Q1-B)") (class "Default")
      (node (ref "Q1") (pin "1") (pinfunction "B_1") (pintype "passive"))
      (node (ref "R25") (pin "2") (pinfunction "2_2") (pintype "passive"))
    )
    (net (code "46") (name "Net-(U3-EN)") (class "Default")
      (node (ref "C7") (pin "2") (pinfunction "2_2") (pintype "passive"))
      (node (ref "F1") (pin "2") (pinfunction "2_2") (pintype "passive"))
      (node (ref "U3") (pin "1") (pinfunction "Vin_1") (pintype "passive"))
      (node (ref "U3") (pin "3") (pinfunction "EN_3") (pintype "passive"))
    )
    (net (code "47") (name "Net-(U4-BOOT)") (class "Default")
      (node (ref "C29") (pin "1") (pinfunction "1_1") (pintype "passive"))
      (node (ref "U4") (pin "1") (pinfunction "BOOT_1") (pintype "passive"))
    )
    (net (code "48") (name "Net-(U4-COMP)") (class "Default")
      (node (ref "C31") (pin "2") (pinfunction "2_2") (pintype "passive"))
      (node (ref "R11") (pin "1") (pinfunction "1_1") (pintype "passive"))
      (node (ref "U4") (pin "6") (pinfunction "COMP_6") (pintype "passive"))
    )
    (net (code "49") (name "Net-(U4-RT{slash}CLK)") (class "Default")
      (node (ref "R10") (pin "1") (pinfunction "1_1") (pintype "passive"))
      (node (ref "U4") (pin "4") (pinfunction "RT/CLK_4") (pintype "passive"))
    )
    (net (code "50") (name "Net-(U6-FB)") (class "Default")
      (node (ref "R1") (pin "1") (pinfunction "1_1") (pintype "passive"))
      (node (ref "R17") (pin "1") (pinfunction "1_1") (pintype "passive"))
      (node (ref "R2") (pin "2") (pinfunction "2_2") (pintype "passive"))
      (node (ref "U6") (pin "3") (pinfunction "FB_3") (pintype "passive"))
    )
    (net (code "51") (name "Net-(U7-ISEN)") (class "Default")
      (node (ref "R8") (pin "2") (pinfunction "2_2") (pintype "passive"))
      (node (ref "U7") (pin "7") (pinfunction "ISEN_7") (pintype "passive"))
    )
    (net (code "52") (name "VCC") (class "Default")
      (node (ref "C2") (pin "2") (pinfunction "2_2") (pintype "passive"))
      (node (ref "C3") (pin "2") (pinfunction "2_2") (pintype "passive"))
      (node (ref "C4") (pin "2") (pinfunction "2_2") (pintype "passive"))
      (node (ref "C5") (pin "2") (pinfunction "2_2") (pintype "passive"))
      (node (ref "OLED") (pin "2") (pinfunction "2_2") (pintype "passive"))
      (node (ref "R1") (pin "2") (pinfunction "2_2") (pintype "passive"))
      (node (ref "U6") (pin "5") (pinfunction "VOUT_5") (pintype "passive"))
    )
    (net (code "53") (name "VO5") (class "Default")
      (node (ref "C1") (pin "2") (pinfunction "2_2") (pintype "passive"))
      (node (ref "C21") (pin "1") (pinfunction "1_1") (pintype "passive"))
      (node (ref "C24") (pin "1") (pinfunction "1_1") (pintype "passive"))
      (node (ref "C32") (pin "1") (pinfunction "1_1") (pintype "passive"))
      (node (ref "C33") (pin "1") (pinfunction "1_1") (pintype "passive"))
      (node (ref "C34") (pin "1") (pinfunction "1_1") (pintype "passive"))
      (node (ref "C35") (pin "1") (pinfunction "1_1") (pintype "passive"))
      (node (ref "F1") (pin "1") (pinfunction "1_1") (pintype "passive"))
      (node (ref "L1") (pin "1") (pinfunction "1_1") (pintype "passive"))
      (node (ref "L2") (pin "2") (pinfunction "2_2") (pintype "passive"))
      (node (ref "OLED") (pin "20") (pinfunction "20_20") (pintype "passive"))
      (node (ref "OLED") (pin "21") (pinfunction "21_21") (pintype "passive"))
      (node (ref "P1") (pin "2") (pinfunction "2_2") (pintype "passive"))
      (node (ref "P2") (pin "2") (pinfunction "2_2") (pintype "passive"))
      (node (ref "R26") (pin "2") (pinfunction "2_2") (pintype "passive"))
      (node (ref "R3") (pin "1") (pinfunction "1_1") (pintype "passive"))
      (node (ref "R5") (pin "1") (pinfunction "1_1") (pintype "passive"))
      (node (ref "R9") (pin "1") (pinfunction "1_1") (pintype "passive"))
      (node (ref "U6") (pin "4") (pinfunction "EN_4") (pintype "passive"))
      (node (ref "U6") (pin "6") (pinfunction "VIN_6") (pintype "passive"))
      (node (ref "XP2") (pin "3") (pinfunction "3_3") (pintype "passive"))
      (node (ref "XP3") (pin "3") (pinfunction "3_3") (pintype "passive"))
    )
    (net (code "54") (name "unconnected-(OLED-Pad18)") (class "Default")
      (node (ref "OLED") (pin "18") (pinfunction "18_18") (pintype "passive+no_connect"))
    )
    (net (code "55") (name "unconnected-(OLED-Pad22)") (class "Default")
      (node (ref "OLED") (pin "22") (pinfunction "22_22") (pintype "passive+no_connect"))
    )
    (net (code "56") (name "unconnected-(OLED-Pad23)") (class "Default")
      (node (ref "OLED") (pin "23") (pinfunction "23_23") (pintype "passive+no_connect"))
    )
    (net (code "57") (name "unconnected-(OLED-Pad24)") (class "Default")
      (node (ref "OLED") (pin "24") (pinfunction "24_24") (pintype "passive+no_connect"))
    )
    (net (code "58") (name "unconnected-(OLED-Pad25)") (class "Default")
      (node (ref "OLED") (pin "25") (pinfunction "25_25") (pintype "passive+no_connect"))
    )
    (net (code "59") (name "unconnected-(OLED-Pad26)") (class "Default")
      (node (ref "OLED") (pin "26") (pinfunction "26_26") (pintype "passive+no_connect"))
    )
    (net (code "60") (name "unconnected-(OLED-Pad27)") (class "Default")
      (node (ref "OLED") (pin "27") (pinfunction "27_27") (pintype "passive+no_connect"))
    )
    (net (code "61") (name "unconnected-(OLED-Pad28)") (class "Default")
      (node (ref "OLED") (pin "28") (pinfunction "28_28") (pintype "passive+no_connect"))
    )
    (net (code "62") (name "unconnected-(OLED-Pad29)") (class "Default")
      (node (ref "OLED") (pin "29") (pinfunction "29_29") (pintype "passive+no_connect"))
    )
    (net (code "63") (name "unconnected-(U1A-PB3-Pad30)") (class "Default")
      (node (ref "U1") (pin "30") (pinfunction "PB3_30") (pintype "bidirectional"))
    )
    (net (code "64") (name "unconnected-(U1A-PB4-Pad31)") (class "Default")
      (node (ref "U1") (pin "31") (pinfunction "PB4_31") (pintype "bidirectional"))
    )
    (net (code "65") (name "unconnected-(U3-NC-Pad4)") (class "Default")
      (node (ref "U3") (pin "4") (pinfunction "NC_4") (pintype "passive+no_connect"))
    )
    (net (code "66") (name "unconnected-(U4-EN-Pad3)") (class "Default")
      (node (ref "U4") (pin "3") (pinfunction "EN_3") (pintype "passive+no_connect"))
    )
    (net (code "67") (name "unconnected-(U5-Rs-Pad8)") (class "Default")
      (node (ref "U5") (pin "8") (pinfunction "Rs_8") (pintype "passive+no_connect"))
    )
    (net (code "68") (name "unconnected-(U5-Vref-Pad5)") (class "Default")
      (node (ref "U5") (pin "5") (pinfunction "Vref_5") (pintype "passive+no_connect"))
    )
    (net (code "69") (name "unconnected-(U7-nFAULT-Pad4)") (class "Default")
      (node (ref "U7") (pin "4") (pinfunction "nFAULT_4") (pintype "passive+no_connect"))
    )
  )
)
